# PCB_V2.net
KiCad netlist of a schematic drawn in Altium Designer
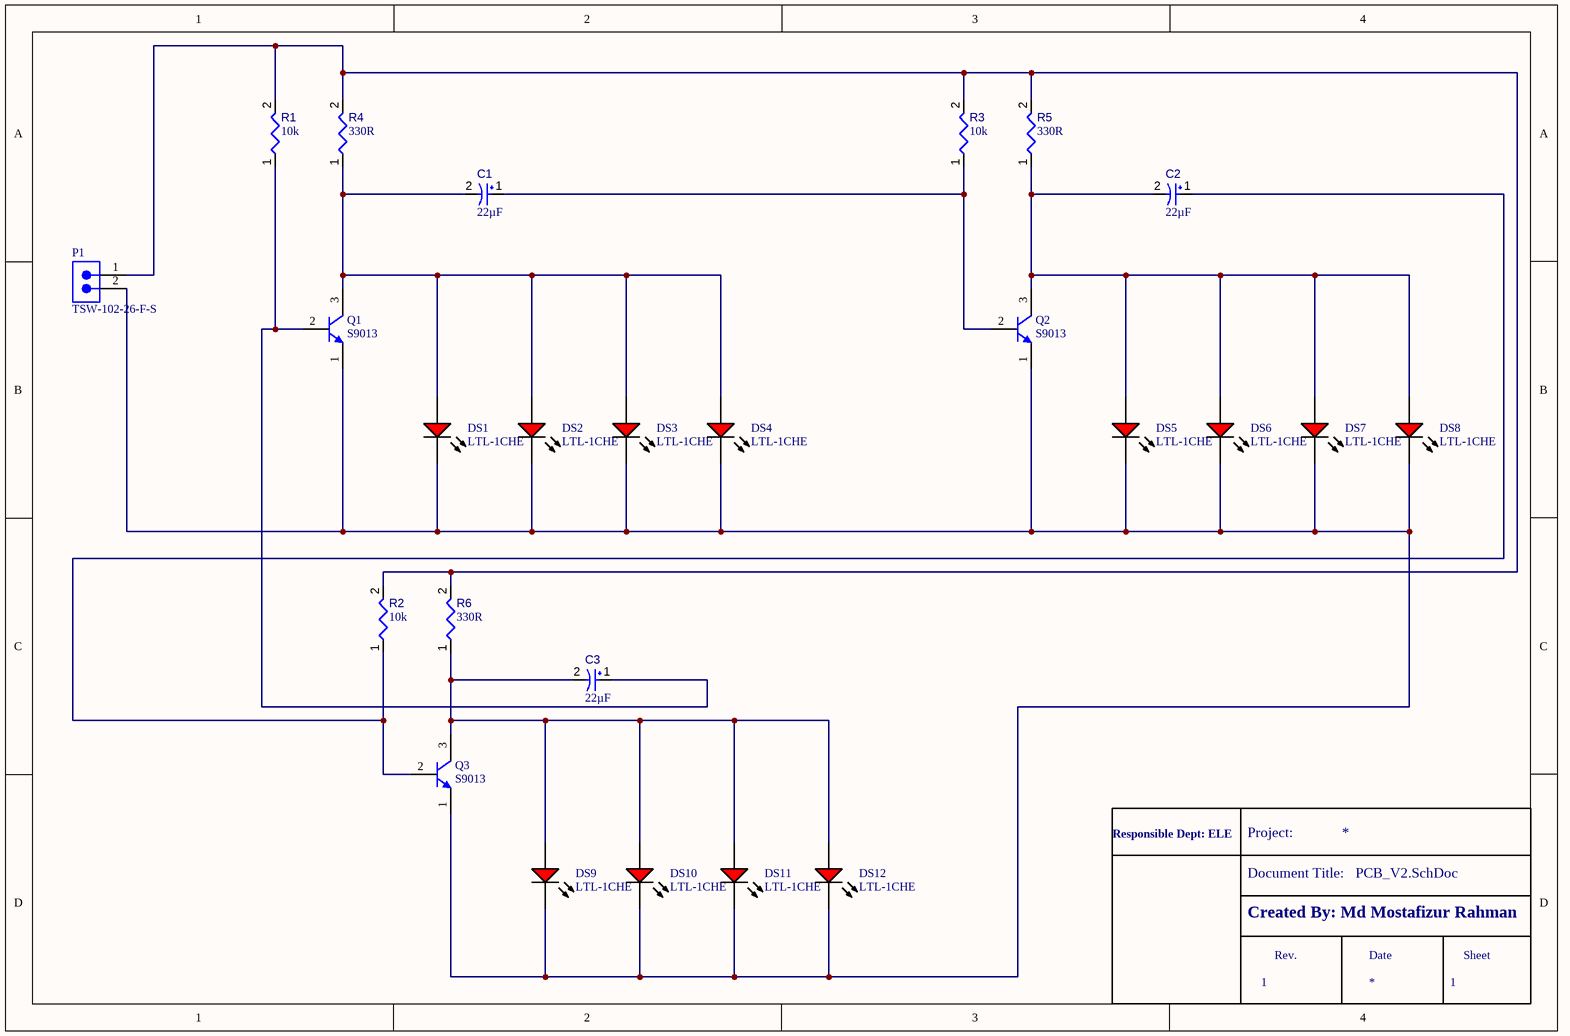
[diagram p0: PCB_V2.SchDoc]

(export (version "E")
  (design (tool "Eeschema 10.0.6"))
  (components
    (comp (ref "*") (value "HSHL Title Block") (libsource (lib "Schlib1") (part "HSHL Title Block")))
    (comp (ref "C1")
      (value "22µF")
      (footprint "CAPPR55-200-1100X500X1200")
      (description "Aluminum Electrolytic Capacitor, 22 uF, +/- 20%, 50 V, -40 to 85 degC, 2-Pin THD, RoHS, Bulk")
      (fields (field (name "MANUFACTURER") "Panasonic") (field (name "TOLERANCE") "20%"))
      (libsource (lib "Md Mostafizur Rahman") (part "CAP-P-2"))
    )
    (comp (ref "C2")
      (value "22µF")
      (footprint "CAPPR55-200-1100X500X1200")
      (description "Aluminum Electrolytic Capacitor, 22 uF, +/- 20%, 50 V, -40 to 85 degC, 2-Pin THD, RoHS, Bulk")
      (fields (field (name "MANUFACTURER") "Panasonic") (field (name "TOLERANCE") "20%"))
      (libsource (lib "Md Mostafizur Rahman") (part "CAP-P-2"))
    )
    (comp (ref "C3")
      (value "22µF")
      (footprint "CAPPR55-200-1100X500X1200")
      (description "Aluminum Electrolytic Capacitor, 22 uF, +/- 20%, 50 V, -40 to 85 degC, 2-Pin THD, RoHS, Bulk")
      (fields (field (name "MANUFACTURER") "Panasonic") (field (name "TOLERANCE") "20%"))
      (libsource (lib "Md Mostafizur Rahman") (part "CAP-P-2"))
    )
    (comp (ref "DS1")
      (value "LTL-1CHE")
      (footprint "INDPR60-254-520X380X650")
      (description "LED Uni-Color Red, 100 mW, 30 mA, -55 to 100 degC, 2-Pin THD, RoHS, Bulk")
      (fields (field (name "MANUFACTURER") "Lite-On"))
      (libsource (lib "Md Mostafizur Rahman") (part "LED-RED-AK-2"))
    )
    (comp (ref "DS2")
      (value "LTL-1CHE")
      (footprint "INDPR60-254-520X380X650")
      (description "LED Uni-Color Red, 100 mW, 30 mA, -55 to 100 degC, 2-Pin THD, RoHS, Bulk")
      (fields (field (name "MANUFACTURER") "Lite-On"))
      (libsource (lib "Md Mostafizur Rahman") (part "LED-RED-AK-2"))
    )
    (comp (ref "DS3")
      (value "LTL-1CHE")
      (footprint "INDPR60-254-520X380X650")
      (description "LED Uni-Color Red, 100 mW, 30 mA, -55 to 100 degC, 2-Pin THD, RoHS, Bulk")
      (fields (field (name "MANUFACTURER") "Lite-On"))
      (libsource (lib "Md Mostafizur Rahman") (part "LED-RED-AK-2"))
    )
    (comp (ref "DS4")
      (value "LTL-1CHE")
      (footprint "INDPR60-254-520X380X650")
      (description "LED Uni-Color Red, 100 mW, 30 mA, -55 to 100 degC, 2-Pin THD, RoHS, Bulk")
      (fields (field (name "MANUFACTURER") "Lite-On"))
      (libsource (lib "Md Mostafizur Rahman") (part "LED-RED-AK-2"))
    )
    (comp (ref "DS5")
      (value "LTL-1CHE")
      (footprint "INDPR60-254-520X380X650")
      (description "LED Uni-Color Red, 100 mW, 30 mA, -55 to 100 degC, 2-Pin THD, RoHS, Bulk")
      (fields (field (name "MANUFACTURER") "Lite-On"))
      (libsource (lib "Md Mostafizur Rahman") (part "LED-RED-AK-2"))
    )
    (comp (ref "DS6")
      (value "LTL-1CHE")
      (footprint "INDPR60-254-520X380X650")
      (description "LED Uni-Color Red, 100 mW, 30 mA, -55 to 100 degC, 2-Pin THD, RoHS, Bulk")
      (fields (field (name "MANUFACTURER") "Lite-On"))
      (libsource (lib "Md Mostafizur Rahman") (part "LED-RED-AK-2"))
    )
    (comp (ref "DS7")
      (value "LTL-1CHE")
      (footprint "INDPR60-254-520X380X650")
      (description "LED Uni-Color Red, 100 mW, 30 mA, -55 to 100 degC, 2-Pin THD, RoHS, Bulk")
      (fields (field (name "MANUFACTURER") "Lite-On"))
      (libsource (lib "Md Mostafizur Rahman") (part "LED-RED-AK-2"))
    )
    (comp (ref "DS8")
      (value "LTL-1CHE")
      (footprint "INDPR60-254-520X380X650")
      (description "LED Uni-Color Red, 100 mW, 30 mA, -55 to 100 degC, 2-Pin THD, RoHS, Bulk")
      (fields (field (name "MANUFACTURER") "Lite-On"))
      (libsource (lib "Md Mostafizur Rahman") (part "LED-RED-AK-2"))
    )
    (comp (ref "DS9")
      (value "LTL-1CHE")
      (footprint "INDPR60-254-520X380X650")
      (description "LED Uni-Color Red, 100 mW, 30 mA, -55 to 100 degC, 2-Pin THD, RoHS, Bulk")
      (fields (field (name "MANUFACTURER") "Lite-On"))
      (libsource (lib "Md Mostafizur Rahman") (part "LED-RED-AK-2"))
    )
    (comp (ref "DS10")
      (value "LTL-1CHE")
      (footprint "INDPR60-254-520X380X650")
      (description "LED Uni-Color Red, 100 mW, 30 mA, -55 to 100 degC, 2-Pin THD, RoHS, Bulk")
      (fields (field (name "MANUFACTURER") "Lite-On"))
      (libsource (lib "Md Mostafizur Rahman") (part "LED-RED-AK-2"))
    )
    (comp (ref "DS11")
      (value "LTL-1CHE")
      (footprint "INDPR60-254-520X380X650")
      (description "LED Uni-Color Red, 100 mW, 30 mA, -55 to 100 degC, 2-Pin THD, RoHS, Bulk")
      (fields (field (name "MANUFACTURER") "Lite-On"))
      (libsource (lib "Md Mostafizur Rahman") (part "LED-RED-AK-2"))
    )
    (comp (ref "DS12")
      (value "LTL-1CHE")
      (footprint "INDPR60-254-520X380X650")
      (description "LED Uni-Color Red, 100 mW, 30 mA, -55 to 100 degC, 2-Pin THD, RoHS, Bulk")
      (fields (field (name "MANUFACTURER") "Lite-On"))
      (libsource (lib "Md Mostafizur Rahman") (part "LED-RED-AK-2"))
    )
    (comp (ref "P1")
      (value "TSW-102-26-F-S")
      (footprint "SMTC-TSW-102-26-XX-S")
      (description "0.025\" SQ Post Header, Through-hole, Vertical, -55 to 125 degC, 2.54 mm Pitch, 2-Pin, Male, RoHS")
      (fields (field (name "MANUFACTURER") "Samtec"))
      (libsource (lib "Altium Content Vault") (part "SMTC-TSW-102-X-X-S-X"))
    )
    (comp (ref "Q1")
      (value "S9013")
      (footprint "JSCJ-TO-92-3_V")
      (description "Transistor, NPN, 0.1 uA, 150 MHz, 3-Pin TO-92")
      (fields (field (name "MANUFACTURER") "Jiangsu Changjiang Electronics Technology"))
      (libsource (lib "Md Mostafizur Rahman") (part "BJT-NPN-EBC-3"))
    )
    (comp (ref "Q2")
      (value "S9013")
      (footprint "JSCJ-TO-92-3_V")
      (description "Transistor, NPN, 0.1 uA, 150 MHz, 3-Pin TO-92")
      (fields (field (name "MANUFACTURER") "Jiangsu Changjiang Electronics Technology"))
      (libsource (lib "Md Mostafizur Rahman") (part "BJT-NPN-EBC-3"))
    )
    (comp (ref "Q3")
      (value "S9013")
      (footprint "JSCJ-TO-92-3_V")
      (description "Transistor, NPN, 0.1 uA, 150 MHz, 3-Pin TO-92")
      (fields (field (name "MANUFACTURER") "Jiangsu Changjiang Electronics Technology"))
      (libsource (lib "Md Mostafizur Rahman") (part "BJT-NPN-EBC-3"))
    )
    (comp (ref "R1")
      (value "10k")
      (footprint "RESA60-630X240")
      (description "Axial Resistor, 10 KOhm, +/- 1%, 0.25 W, -55 to 155 degC, 2-Pin THD, RoHS, Bulk")
      (fields (field (name "TOLERANCE") "1%") (field (name "POWER") "250mW"))
      (libsource (lib "Md Mostafizur Rahman") (part "RES-2"))
    )
    (comp (ref "R2")
      (value "10k")
      (footprint "RESA60-630X240")
      (description "Axial Resistor, 10 KOhm, +/- 1%, 0.25 W, -55 to 155 degC, 2-Pin THD, RoHS, Bulk")
      (fields (field (name "TOLERANCE") "1%") (field (name "POWER") "250mW"))
      (libsource (lib "Md Mostafizur Rahman") (part "RES-2"))
    )
    (comp (ref "R3")
      (value "10k")
      (footprint "RESA60-630X240")
      (description "Axial Resistor, 10 KOhm, +/- 1%, 0.25 W, -55 to 155 degC, 2-Pin THD, RoHS, Bulk")
      (fields (field (name "TOLERANCE") "1%") (field (name "POWER") "250mW"))
      (libsource (lib "Md Mostafizur Rahman") (part "RES-2"))
    )
    (comp (ref "R4")
      (value "330R")
      (footprint "RESA60-630X240")
      (description "Axial Resistor, 10 KOhm, +/- 1%, 0.25 W, -55 to 155 degC, 2-Pin THD, RoHS, Bulk")
      (fields (field (name "TOLERANCE") "1%") (field (name "POWER") "250mW"))
      (libsource (lib "Md Mostafizur Rahman") (part "RES-2"))
    )
    (comp (ref "R5")
      (value "330R")
      (footprint "RESA60-630X240")
      (description "Axial Resistor, 10 KOhm, +/- 1%, 0.25 W, -55 to 155 degC, 2-Pin THD, RoHS, Bulk")
      (fields (field (name "TOLERANCE") "1%") (field (name "POWER") "250mW"))
      (libsource (lib "Md Mostafizur Rahman") (part "RES-2"))
    )
    (comp (ref "R6")
      (value "330R")
      (footprint "RESA60-630X240")
      (description "Axial Resistor, 10 KOhm, +/- 1%, 0.25 W, -55 to 155 degC, 2-Pin THD, RoHS, Bulk")
      (fields (field (name "TOLERANCE") "1%") (field (name "POWER") "250mW"))
      (libsource (lib "Md Mostafizur Rahman") (part "RES-2"))
    )
  )
  (nets
    (net (code "1") (name "Net-(DS1-A)") (class "Default")
      (node (ref "C1") (pin "2") (pinfunction "2_2") (pintype "passive"))
      (node (ref "DS1") (pin "1") (pinfunction "A_1") (pintype "passive"))
      (node (ref "DS2") (pin "1") (pinfunction "A_1") (pintype "passive"))
      (node (ref "DS3") (pin "1") (pinfunction "A_1") (pintype "passive"))
      (node (ref "DS4") (pin "1") (pinfunction "A_1") (pintype "passive"))
      (node (ref "Q1") (pin "3") (pinfunction "C_3") (pintype "passive"))
      (node (ref "R4") (pin "1") (pinfunction "1_1") (pintype "passive"))
    )
    (net (code "2") (name "Net-(DS1-K)") (class "Default")
      (node (ref "DS1") (pin "2") (pinfunction "K_2") (pintype "passive"))
      (node (ref "DS10") (pin "2") (pinfunction "K_2") (pintype "passive"))
      (node (ref "DS11") (pin "2") (pinfunction "K_2") (pintype "passive"))
      (node (ref "DS12") (pin "2") (pinfunction "K_2") (pintype "passive"))
      (node (ref "DS2") (pin "2") (pinfunction "K_2") (pintype "passive"))
      (node (ref "DS3") (pin "2") (pinfunction "K_2") (pintype "passive"))
      (node (ref "DS4") (pin "2") (pinfunction "K_2") (pintype "passive"))
      (node (ref "DS5") (pin "2") (pinfunction "K_2") (pintype "passive"))
      (node (ref "DS6") (pin "2") (pinfunction "K_2") (pintype "passive"))
      (node (ref "DS7") (pin "2") (pinfunction "K_2") (pintype "passive"))
      (node (ref "DS8") (pin "2") (pinfunction "K_2") (pintype "passive"))
      (node (ref "DS9") (pin "2") (pinfunction "K_2") (pintype "passive"))
      (node (ref "P1") (pin "2") (pinfunction "2_2") (pintype "passive"))
      (node (ref "Q1") (pin "1") (pinfunction "E_1") (pintype "passive"))
      (node (ref "Q2") (pin "1") (pinfunction "E_1") (pintype "passive"))
      (node (ref "Q3") (pin "1") (pinfunction "E_1") (pintype "passive"))
    )
    (net (code "3") (name "Net-(DS5-A)") (class "Default")
      (node (ref "C2") (pin "2") (pinfunction "2_2") (pintype "passive"))
      (node (ref "DS5") (pin "1") (pinfunction "A_1") (pintype "passive"))
      (node (ref "DS6") (pin "1") (pinfunction "A_1") (pintype "passive"))
      (node (ref "DS7") (pin "1") (pinfunction "A_1") (pintype "passive"))
      (node (ref "DS8") (pin "1") (pinfunction "A_1") (pintype "passive"))
      (node (ref "Q2") (pin "3") (pinfunction "C_3") (pintype "passive"))
      (node (ref "R5") (pin "1") (pinfunction "1_1") (pintype "passive"))
    )
    (net (code "4") (name "Net-(DS10-A)") (class "Default")
      (node (ref "C3") (pin "2") (pinfunction "2_2") (pintype "passive"))
      (node (ref "DS10") (pin "1") (pinfunction "A_1") (pintype "passive"))
      (node (ref "DS11") (pin "1") (pinfunction "A_1") (pintype "passive"))
      (node (ref "DS12") (pin "1") (pinfunction "A_1") (pintype "passive"))
      (node (ref "DS9") (pin "1") (pinfunction "A_1") (pintype "passive"))
      (node (ref "Q3") (pin "3") (pinfunction "C_3") (pintype "passive"))
      (node (ref "R6") (pin "1") (pinfunction "1_1") (pintype "passive"))
    )
    (net (code "5") (name "Net-(P1-Pad1)") (class "Default")
      (node (ref "P1") (pin "1") (pinfunction "1_1") (pintype "passive"))
      (node (ref "R1") (pin "2") (pinfunction "2_2") (pintype "passive"))
      (node (ref "R2") (pin "2") (pinfunction "2_2") (pintype "passive"))
      (node (ref "R3") (pin "2") (pinfunction "2_2") (pintype "passive"))
      (node (ref "R4") (pin "2") (pinfunction "2_2") (pintype "passive"))
      (node (ref "R5") (pin "2") (pinfunction "2_2") (pintype "passive"))
      (node (ref "R6") (pin "2") (pinfunction "2_2") (pintype "passive"))
    )
    (net (code "6") (name "Net-(Q1-B)") (class "Default")
      (node (ref "C3") (pin "1") (pinfunction "1_1") (pintype "passive"))
      (node (ref "Q1") (pin "2") (pinfunction "B_2") (pintype "passive"))
      (node (ref "R1") (pin "1") (pinfunction "1_1") (pintype "passive"))
    )
    (net (code "7") (name "Net-(Q2-B)") (class "Default")
      (node (ref "C1") (pin "1") (pinfunction "1_1") (pintype "passive"))
      (node (ref "Q2") (pin "2") (pinfunction "B_2") (pintype "passive"))
      (node (ref "R3") (pin "1") (pinfunction "1_1") (pintype "passive"))
    )
    (net (code "8") (name "Net-(Q3-B)") (class "Default")
      (node (ref "C2") (pin "1") (pinfunction "1_1") (pintype "passive"))
      (node (ref "Q3") (pin "2") (pinfunction "B_2") (pintype "passive"))
      (node (ref "R2") (pin "1") (pinfunction "1_1") (pintype "passive"))
    )
  )
)
